# PROTOshield.net
KiCad netlist of a schematic drawn in EAGLE
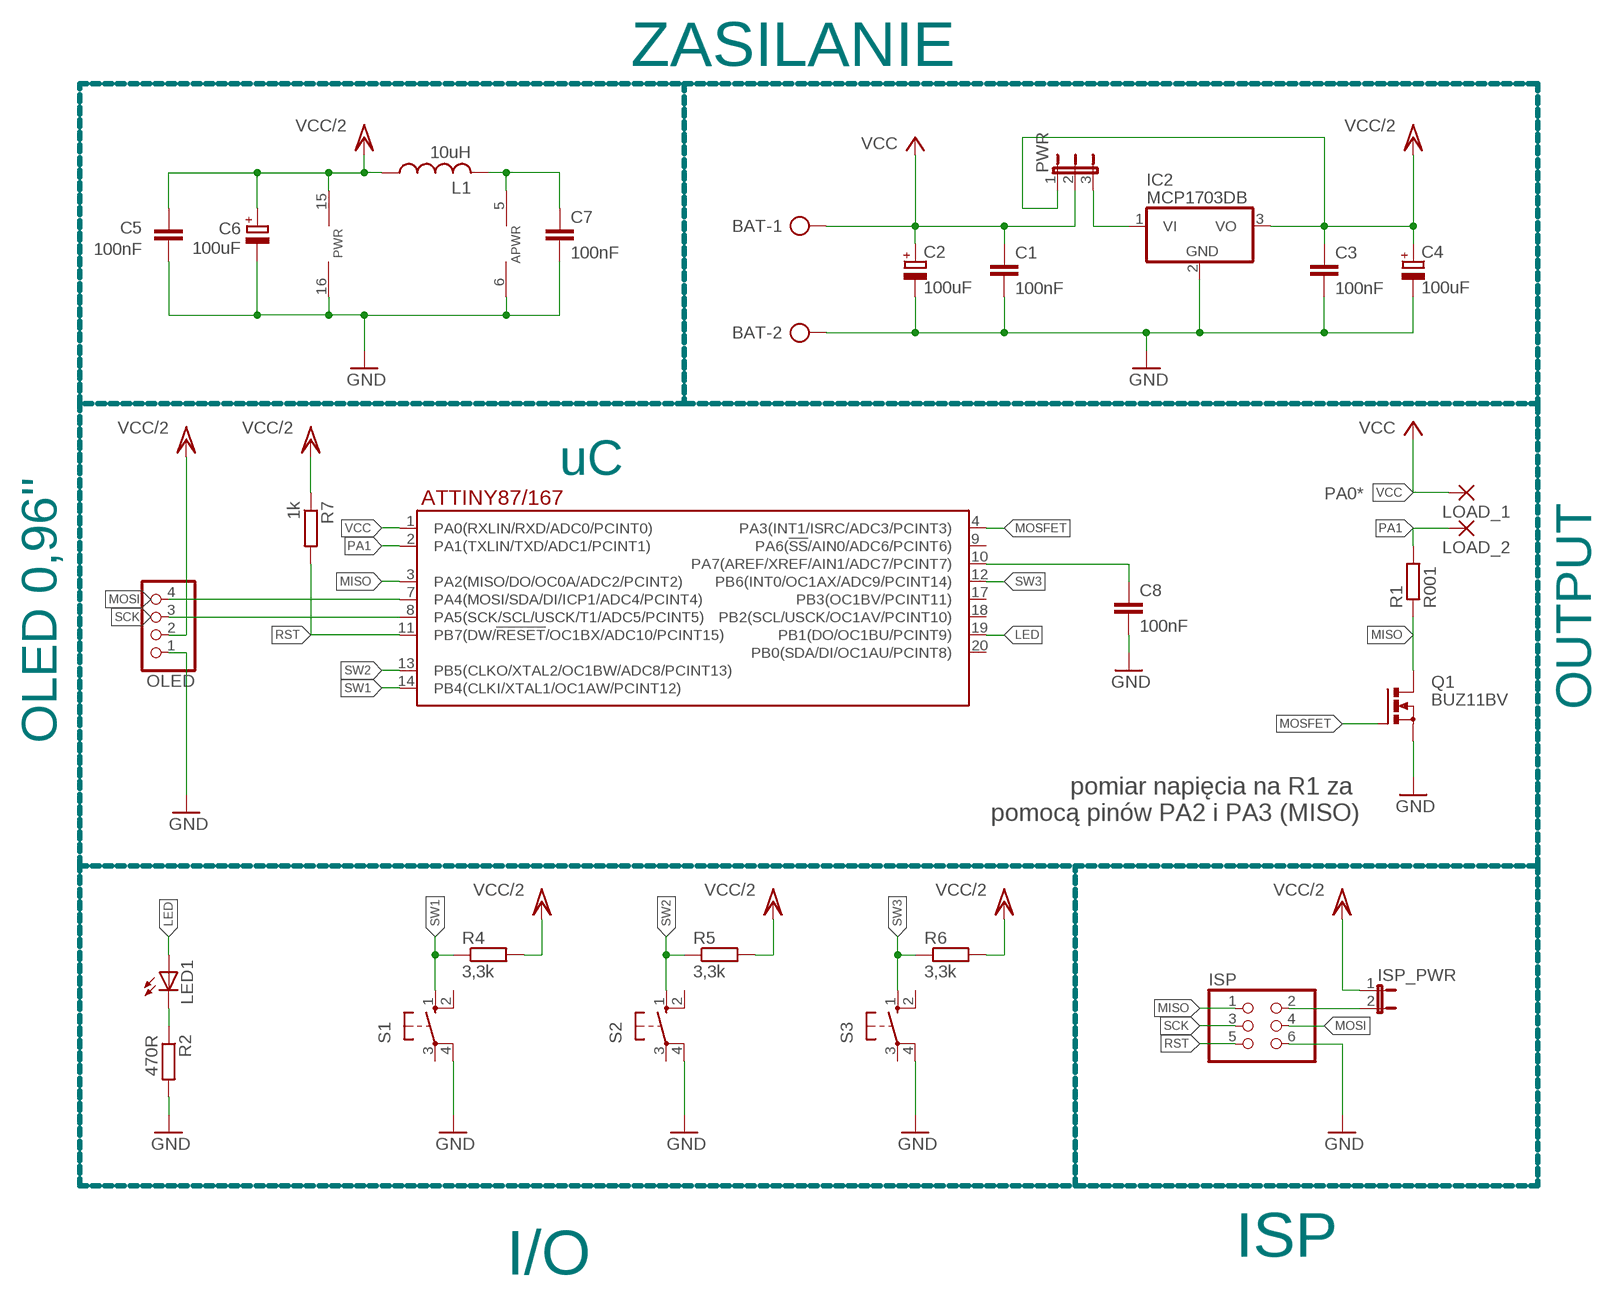
[diagram p0: schematic, sheet 1]

(export (version "E")
  (design (tool "Eeschema 10.0.6"))
  (components
    (comp (ref "BAT")
      (value "AK300/2")
      (footprint "eagle-import:AK300_2")
      (libsource (lib "eagle-import") (part "AK300/2"))
    )
    (comp (ref "C1")
      (value "100nF")
      (footprint "eagle-import:C050-045X075")
      (libsource (lib "eagle-import") (part "C-EU050-045X075"))
    )
    (comp (ref "C2")
      (value "100uF")
      (footprint "eagle-import:E3,5-8")
      (libsource (lib "eagle-import") (part "CPOL-EUE3.5-8"))
    )
    (comp (ref "C3")
      (value "100nF")
      (footprint "eagle-import:C050-045X075")
      (libsource (lib "eagle-import") (part "C-EU050-045X075"))
    )
    (comp (ref "C4")
      (value "100uF")
      (footprint "eagle-import:E3,5-8")
      (libsource (lib "eagle-import") (part "CPOL-EUE3.5-8"))
    )
    (comp (ref "C5")
      (value "100nF")
      (footprint "eagle-import:C050-045X075")
      (libsource (lib "eagle-import") (part "C-EU050-045X075"))
    )
    (comp (ref "C6")
      (value "100uF")
      (footprint "eagle-import:E3,5-8")
      (libsource (lib "eagle-import") (part "CPOL-EUE3.5-8"))
    )
    (comp (ref "C7")
      (value "100nF")
      (footprint "eagle-import:C050-045X075")
      (libsource (lib "eagle-import") (part "C-EU050-045X075"))
    )
    (comp (ref "C8")
      (value "100nF")
      (footprint "eagle-import:C050-045X075")
      (libsource (lib "eagle-import") (part "C-EU050-045X075"))
    )
    (comp (ref "IC2")
      (value "MCP1703DB")
      (footprint "eagle-import:SOT223")
      (libsource (lib "eagle-import") (part "MCP1703DB"))
    )
    (comp (ref "ISP")
      (value "PINHD-2X3")
      (footprint "eagle-import:2X03")
      (libsource (lib "eagle-import") (part "PINHD-2X3"))
    )
    (comp (ref "ISP_PWR")
      (value "JP1E")
      (footprint "eagle-import:JP1")
      (libsource (lib "eagle-import") (part "JP1E"))
    )
    (comp (ref "L1")
      (value "10uH")
      (footprint "eagle-import:0207_7")
      (libsource (lib "eagle-import") (part "L-US0207/7"))
    )
    (comp (ref "LED1")
      (value "LED5MM")
      (footprint "eagle-import:LED5MM")
      (libsource (lib "eagle-import") (part "LED5MM"))
    )
    (comp (ref "LOAD_1")
      (value "3,81/1,3")
      (footprint "eagle-import:3,81_1,3")
      (libsource (lib "eagle-import") (part "3,81/1,3"))
    )
    (comp (ref "LOAD_2")
      (value "3,81/1,3")
      (footprint "eagle-import:3,81_1,3")
      (libsource (lib "eagle-import") (part "3,81/1,3"))
    )
    (comp (ref "OLED")
      (value "PINHD-1X4")
      (footprint "eagle-import:1X04")
      (libsource (lib "eagle-import") (part "PINHD-1X4"))
    )
    (comp (ref "PWR")
      (value "JP2E")
      (footprint "eagle-import:JP2")
      (libsource (lib "eagle-import") (part "JP2E"))
    )
    (comp (ref "Q1")
      (value "BUZ11BV")
      (footprint "eagle-import:TO220BV")
      (libsource (lib "eagle-import") (part "BUZ11BV"))
    )
    (comp (ref "R1")
      (value "R001")
      (footprint "eagle-import:R2512")
      (libsource (lib "eagle-import") (part "R-EU_R2512"))
    )
    (comp (ref "R2")
      (value "470R")
      (footprint "eagle-import:R1206")
      (libsource (lib "eagle-import") (part "R-EU_R1206"))
    )
    (comp (ref "R4")
      (value "3,3k")
      (footprint "eagle-import:R1206")
      (libsource (lib "eagle-import") (part "R-EU_R1206"))
    )
    (comp (ref "R5")
      (value "3,3k")
      (footprint "eagle-import:R1206")
      (libsource (lib "eagle-import") (part "R-EU_R1206"))
    )
    (comp (ref "R6")
      (value "3,3k")
      (footprint "eagle-import:R1206")
      (libsource (lib "eagle-import") (part "R-EU_R1206"))
    )
    (comp (ref "R7")
      (value "1k")
      (footprint "eagle-import:R1206")
      (libsource (lib "eagle-import") (part "R-EU_R1206"))
    )
    (comp (ref "S1")
      (value "10-XX")
      (footprint "eagle-import:B3F-10XX")
      (fields (field (name "MPN") "B3F-1000"))
      (libsource (lib "eagle-import") (part "10-XX"))
    )
    (comp (ref "S2")
      (value "10-XX")
      (footprint "eagle-import:B3F-10XX")
      (fields (field (name "MPN") "B3F-1000"))
      (libsource (lib "eagle-import") (part "10-XX"))
    )
    (comp (ref "S3")
      (value "10-XX")
      (footprint "eagle-import:B3F-10XX")
      (fields (field (name "MPN") "B3F-1000"))
      (libsource (lib "eagle-import") (part "10-XX"))
    )
    (comp (ref "U$1")
      (value "ATTINY87/167")
      (footprint "eagle-import:SOIC127P1032X265-20N")
      (libsource (lib "eagle-import") (part "ATTINY87/167"))
    )
  )
  (nets
    (net (code "1") (name "GND") (class "Default")
      (node (ref "BAT") (pin "2") (pinfunction "KL_2") (pintype "passive"))
      (node (ref "C1") (pin "2") (pinfunction "2_2") (pintype "passive"))
      (node (ref "C2") (pin "-") (pinfunction "-_-") (pintype "passive"))
      (node (ref "C3") (pin "2") (pinfunction "2_2") (pintype "passive"))
      (node (ref "C4") (pin "-") (pinfunction "-_-") (pintype "passive"))
      (node (ref "C5") (pin "2") (pinfunction "2_2") (pintype "passive"))
      (node (ref "C6") (pin "-") (pinfunction "-_-") (pintype "passive"))
      (node (ref "C7") (pin "2") (pinfunction "2_2") (pintype "passive"))
      (node (ref "C8") (pin "2") (pinfunction "2_2") (pintype "passive"))
      (node (ref "IC2") (pin "2") (pinfunction "GND_2") (pintype "passive"))
      (node (ref "ISP") (pin "6") (pinfunction "6_6") (pintype "passive"))
      (node (ref "OLED") (pin "1") (pinfunction "1_1") (pintype "passive"))
      (node (ref "Q1") (pin "S") (pinfunction "S_S") (pintype "passive"))
      (node (ref "R2") (pin "2") (pinfunction "2_2") (pintype "passive"))
      (node (ref "S1") (pin "4") (pinfunction "P1_4") (pintype "passive"))
      (node (ref "S2") (pin "4") (pinfunction "P1_4") (pintype "passive"))
      (node (ref "S3") (pin "4") (pinfunction "P1_4") (pintype "passive"))
      (node (ref "U$1") (pin "16") (pinfunction "GND_16") (pintype "bidirectional"))
      (node (ref "U$1") (pin "6") (pinfunction "AGND_6") (pintype "bidirectional"))
    )
    (net (code "2") (name "LED") (class "Default")
      (node (ref "LED1") (pin "A") (pinfunction "A_A") (pintype "passive"))
      (node (ref "U$1") (pin "19") (pinfunction "PB1(DO/OC1BU/PCINT9)_19") (pintype "bidirectional"))
    )
    (net (code "3") (name "MISO") (class "Default")
      (node (ref "ISP") (pin "1") (pinfunction "1_1") (pintype "passive"))
      (node (ref "Q1") (pin "D") (pinfunction "D_D") (pintype "passive"))
      (node (ref "R1") (pin "1") (pinfunction "1_1") (pintype "passive"))
      (node (ref "U$1") (pin "3") (pinfunction "PA2(MISO/DO/OC0A/ADC2/PCINT2)_3") (pintype "bidirectional"))
    )
    (net (code "4") (name "MOSFET") (class "Default")
      (node (ref "Q1") (pin "G") (pinfunction "G_G") (pintype "passive"))
      (node (ref "U$1") (pin "4") (pinfunction "PA3(INT1/ISRC/ADC3/PCINT3)_4") (pintype "bidirectional"))
    )
    (net (code "5") (name "MOSI") (class "Default")
      (node (ref "ISP") (pin "4") (pinfunction "4_4") (pintype "passive"))
      (node (ref "OLED") (pin "4") (pinfunction "4_4") (pintype "passive"))
      (node (ref "U$1") (pin "7") (pinfunction "PA4(MOSI/SDA/DI/ICP1/ADC4/PCINT4)_7") (pintype "bidirectional"))
    )
    (net (code "6") (name "Net-(IC2-VI)") (class "Default")
      (node (ref "IC2") (pin "1") (pinfunction "VI_1") (pintype "input"))
      (node (ref "PWR") (pin "3") (pinfunction "3_3") (pintype "passive"))
    )
    (net (code "7") (name "Net-(ISP-Pad2)") (class "Default")
      (node (ref "ISP") (pin "2") (pinfunction "2_2") (pintype "passive"))
      (node (ref "ISP_PWR") (pin "2") (pinfunction "2_2") (pintype "passive"))
    )
    (net (code "8") (name "Net-(LED1-C)") (class "Default")
      (node (ref "LED1") (pin "K") (pinfunction "C_K") (pintype "passive"))
      (node (ref "R2") (pin "1") (pinfunction "1_1") (pintype "passive"))
    )
    (net (code "9") (name "Net-(U$1A-PA7(AREF{slash}XREF{slash}AIN1{slash}ADC7{slash}PCINT7))") (class "Default")
      (node (ref "C8") (pin "1") (pinfunction "1_1") (pintype "passive"))
      (node (ref "U$1") (pin "10") (pinfunction "PA7(AREF/XREF/AIN1/ADC7/PCINT7)_10") (pintype "bidirectional"))
    )
    (net (code "10") (name "Net-(U$1C-AVCC)") (class "Default")
      (node (ref "C7") (pin "1") (pinfunction "1_1") (pintype "passive"))
      (node (ref "L1") (pin "2") (pinfunction "2_2") (pintype "passive"))
      (node (ref "U$1") (pin "5") (pinfunction "AVCC_5") (pintype "bidirectional"))
    )
    (net (code "11") (name "PA1") (class "Default")
      (node (ref "LOAD_2") (pin "1") (pinfunction "P_1") (pintype "passive"))
      (node (ref "R1") (pin "2") (pinfunction "2_2") (pintype "passive"))
      (node (ref "U$1") (pin "2") (pinfunction "PA1(TXLIN/TXD/ADC1/PCINT1)_2") (pintype "bidirectional"))
    )
    (net (code "12") (name "RST") (class "Default")
      (node (ref "ISP") (pin "5") (pinfunction "5_5") (pintype "passive"))
      (node (ref "R7") (pin "2") (pinfunction "2_2") (pintype "passive"))
      (node (ref "U$1") (pin "11") (pinfunction "PB7(DW/~{RESET}/OC1BX/ADC10/PCINT15)_11") (pintype "bidirectional"))
    )
    (net (code "13") (name "SCK") (class "Default")
      (node (ref "ISP") (pin "3") (pinfunction "3_3") (pintype "passive"))
      (node (ref "OLED") (pin "3") (pinfunction "3_3") (pintype "passive"))
      (node (ref "U$1") (pin "8") (pinfunction "PA5(SCK/SCL/USCK/T1/ADC5/PCINT5)_8") (pintype "bidirectional"))
    )
    (net (code "14") (name "SW1") (class "Default")
      (node (ref "R4") (pin "1") (pinfunction "1_1") (pintype "passive"))
      (node (ref "S1") (pin "1") (pinfunction "S_1") (pintype "passive"))
      (node (ref "U$1") (pin "14") (pinfunction "PB4(CLKI/XTAL1/OC1AW/PCINT12)_14") (pintype "bidirectional"))
    )
    (net (code "15") (name "SW2") (class "Default")
      (node (ref "R5") (pin "1") (pinfunction "1_1") (pintype "passive"))
      (node (ref "S2") (pin "1") (pinfunction "S_1") (pintype "passive"))
      (node (ref "U$1") (pin "13") (pinfunction "PB5(CLKO/XTAL2/OC1BW/ADC8/PCINT13)_13") (pintype "bidirectional"))
    )
    (net (code "16") (name "SW3") (class "Default")
      (node (ref "R6") (pin "1") (pinfunction "1_1") (pintype "passive"))
      (node (ref "S3") (pin "1") (pinfunction "S_1") (pintype "passive"))
      (node (ref "U$1") (pin "12") (pinfunction "PB6(INT0/OC1AX/ADC9/PCINT14)_12") (pintype "bidirectional"))
    )
    (net (code "17") (name "VCC") (class "Default")
      (node (ref "BAT") (pin "1") (pinfunction "KL_1") (pintype "passive"))
      (node (ref "C1") (pin "1") (pinfunction "1_1") (pintype "passive"))
      (node (ref "C2") (pin "+") (pinfunction "+_+") (pintype "passive"))
      (node (ref "LOAD_1") (pin "1") (pinfunction "P_1") (pintype "passive"))
      (node (ref "PWR") (pin "2") (pinfunction "2_2") (pintype "passive"))
      (node (ref "U$1") (pin "1") (pinfunction "PA0(RXLIN/RXD/ADC0/PCINT0)_1") (pintype "bidirectional"))
    )
    (net (code "18") (name "VCC{slash}2") (class "Default")
      (node (ref "C3") (pin "1") (pinfunction "1_1") (pintype "passive"))
      (node (ref "C4") (pin "+") (pinfunction "+_+") (pintype "passive"))
      (node (ref "C5") (pin "1") (pinfunction "1_1") (pintype "passive"))
      (node (ref "C6") (pin "+") (pinfunction "+_+") (pintype "passive"))
      (node (ref "IC2") (pin "3") (pinfunction "VO_3") (pintype "passive"))
      (node (ref "ISP_PWR") (pin "1") (pinfunction "1_1") (pintype "passive"))
      (node (ref "L1") (pin "1") (pinfunction "1_1") (pintype "passive"))
      (node (ref "OLED") (pin "2") (pinfunction "2_2") (pintype "passive"))
      (node (ref "PWR") (pin "1") (pinfunction "1_1") (pintype "passive"))
      (node (ref "R4") (pin "2") (pinfunction "2_2") (pintype "passive"))
      (node (ref "R5") (pin "2") (pinfunction "2_2") (pintype "passive"))
      (node (ref "R6") (pin "2") (pinfunction "2_2") (pintype "passive"))
      (node (ref "R7") (pin "1") (pinfunction "1_1") (pintype "passive"))
      (node (ref "U$1") (pin "15") (pinfunction "VCC_15") (pintype "bidirectional"))
    )
    (net (code "19") (name "unconnected-(S1-P-Pad3)") (class "Default")
      (node (ref "S1") (pin "3") (pinfunction "P_3") (pintype "passive"))
    )
    (net (code "20") (name "unconnected-(S1-S1-Pad2)") (class "Default")
      (node (ref "S1") (pin "2") (pinfunction "S1_2") (pintype "passive"))
    )
    (net (code "21") (name "unconnected-(S2-P-Pad3)") (class "Default")
      (node (ref "S2") (pin "3") (pinfunction "P_3") (pintype "passive"))
    )
    (net (code "22") (name "unconnected-(S2-S1-Pad2)") (class "Default")
      (node (ref "S2") (pin "2") (pinfunction "S1_2") (pintype "passive"))
    )
    (net (code "23") (name "unconnected-(S3-P-Pad3)") (class "Default")
      (node (ref "S3") (pin "3") (pinfunction "P_3") (pintype "passive"))
    )
    (net (code "24") (name "unconnected-(S3-S1-Pad2)") (class "Default")
      (node (ref "S3") (pin "2") (pinfunction "S1_2") (pintype "passive"))
    )
    (net (code "25") (name "unconnected-(U$1A-PA6(~{SS}{slash}AIN0{slash}ADC6{slash}PCINT6)-Pad9)") (class "Default")
      (node (ref "U$1") (pin "9") (pinfunction "PA6(~{SS}/AIN0/ADC6/PCINT6)_9") (pintype "bidirectional"))
    )
    (net (code "26") (name "unconnected-(U$1A-PB0(SDA{slash}DI{slash}OC1AU{slash}PCINT8)-Pad20)") (class "Default")
      (node (ref "U$1") (pin "20") (pinfunction "PB0(SDA/DI/OC1AU/PCINT8)_20") (pintype "bidirectional"))
    )
    (net (code "27") (name "unconnected-(U$1A-PB2(SCL{slash}USCK{slash}OC1AV{slash}PCINT10)-Pad18)") (class "Default")
      (node (ref "U$1") (pin "18") (pinfunction "PB2(SCL/USCK/OC1AV/PCINT10)_18") (pintype "bidirectional"))
    )
    (net (code "28") (name "unconnected-(U$1A-PB3(OC1BV{slash}PCINT11)-Pad17)") (class "Default")
      (node (ref "U$1") (pin "17") (pinfunction "PB3(OC1BV/PCINT11)_17") (pintype "bidirectional"))
    )
  )
)
